# Sheet2.net
KiCad netlist of a schematic drawn in Altium Designer
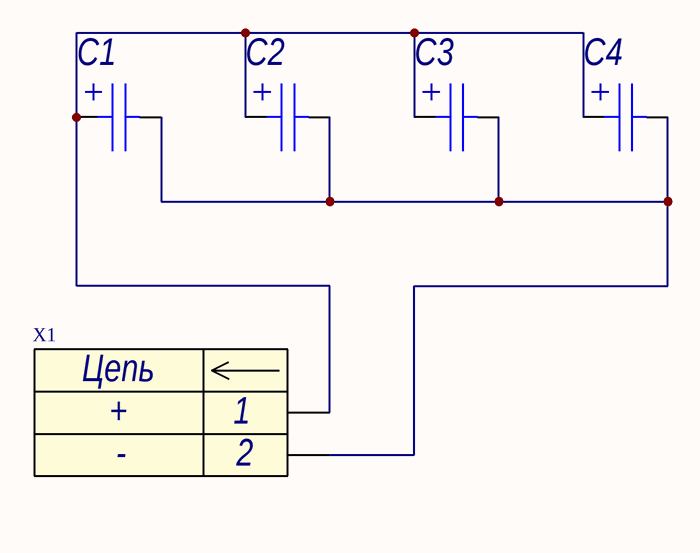
[diagram p0: Sheet2.SchDoc]

(export (version "E")
  (design (tool "Eeschema 10.0.6"))
  (components
    (comp (ref "C1")
      (value "~")
      (footprint "Cap R25 L40")
      (description "Конденсатор пол.")
      (libsource (lib "LibSCH") (part "Capacitor electrolytic"))
    )
    (comp (ref "C2")
      (value "~")
      (footprint "Cap R25 L40")
      (description "Конденсатор пол.")
      (libsource (lib "LibSCH") (part "Capacitor electrolytic"))
    )
    (comp (ref "C3")
      (value "~")
      (footprint "Cap R25 L40")
      (description "Конденсатор пол.")
      (libsource (lib "LibSCH") (part "Capacitor electrolytic"))
    )
    (comp (ref "C4")
      (value "~")
      (footprint "Cap R25 L40")
      (description "Конденсатор пол.")
      (libsource (lib "LibSCH") (part "Capacitor electrolytic"))
    )
    (comp (ref "X1")
      (value "~")
      (footprint "Contact_16AWG")
      (description "Разъем - 2 конт. вилка")
      (libsource (lib "LibSCH") (part "Header_2_plg"))
    )
  )
  (nets
    (net (code "1") (name "Net-(C1-Pad1)") (class "Default")
      (node (ref "C1") (pin "1") (pinfunction "1_1") (pintype "passive"))
      (node (ref "C2") (pin "1") (pinfunction "1_1") (pintype "passive"))
      (node (ref "C3") (pin "1") (pinfunction "1_1") (pintype "passive"))
      (node (ref "C4") (pin "1") (pinfunction "1_1") (pintype "passive"))
      (node (ref "X1") (pin "1") (pinfunction "1_1") (pintype "passive"))
    )
    (net (code "2") (name "Net-(C1-Pad2)") (class "Default")
      (node (ref "C1") (pin "2") (pinfunction "2_2") (pintype "passive"))
      (node (ref "C2") (pin "2") (pinfunction "2_2") (pintype "passive"))
      (node (ref "C3") (pin "2") (pinfunction "2_2") (pintype "passive"))
      (node (ref "C4") (pin "2") (pinfunction "2_2") (pintype "passive"))
      (node (ref "X1") (pin "2") (pinfunction "2_2") (pintype "passive"))
    )
  )
)
